# Test_Points.net
KiCad netlist of a schematic drawn in Altium Designer
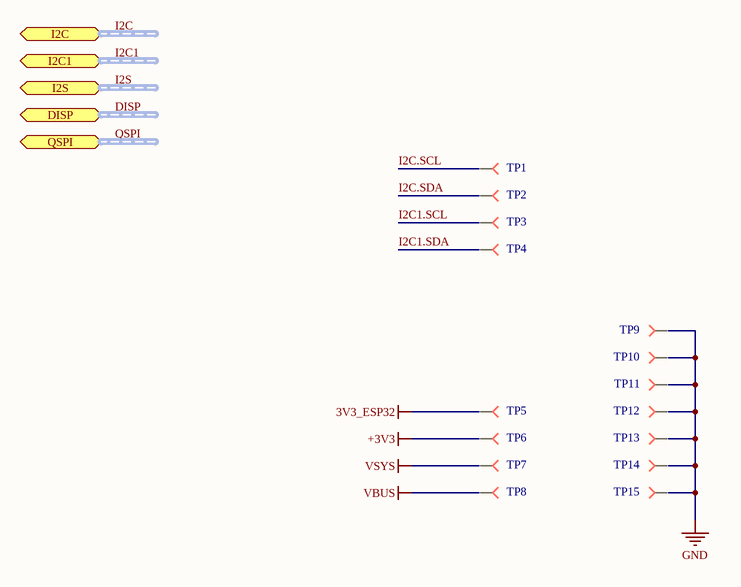
[diagram p0: Test_Points.SchDoc]

(export (version "E")
  (design (tool "Eeschema 10.0.6"))
  (components
    (comp (ref "TP1")
      (value "Test Point Pad")
      (footprint "Testpoint")
      (description "Test Point. There is nothing to buy or mount.")
      (libsource (lib "BLDC_Motor_Driver") (part "Test Point Pad"))
    )
    (comp (ref "TP2")
      (value "Test Point Pad")
      (footprint "Testpoint")
      (description "Test Point. There is nothing to buy or mount.")
      (libsource (lib "BLDC_Motor_Driver") (part "Test Point Pad"))
    )
    (comp (ref "TP3")
      (value "Test Point Pad")
      (footprint "Testpoint")
      (description "Test Point. There is nothing to buy or mount.")
      (libsource (lib "BLDC_Motor_Driver") (part "Test Point Pad"))
    )
    (comp (ref "TP4")
      (value "Test Point Pad")
      (footprint "Testpoint")
      (description "Test Point. There is nothing to buy or mount.")
      (libsource (lib "BLDC_Motor_Driver") (part "Test Point Pad"))
    )
    (comp (ref "TP5")
      (value "Test Point Pad")
      (footprint "Testpoint")
      (description "Test Point. There is nothing to buy or mount.")
      (libsource (lib "BLDC_Motor_Driver") (part "Test Point Pad"))
    )
    (comp (ref "TP6")
      (value "Test Point Pad")
      (footprint "Testpoint")
      (description "Test Point. There is nothing to buy or mount.")
      (libsource (lib "BLDC_Motor_Driver") (part "Test Point Pad"))
    )
    (comp (ref "TP7")
      (value "Test Point Pad")
      (footprint "Testpoint")
      (description "Test Point. There is nothing to buy or mount.")
      (libsource (lib "BLDC_Motor_Driver") (part "Test Point Pad"))
    )
    (comp (ref "TP8")
      (value "Test Point Pad")
      (footprint "Testpoint")
      (description "Test Point. There is nothing to buy or mount.")
      (libsource (lib "BLDC_Motor_Driver") (part "Test Point Pad"))
    )
    (comp (ref "TP9")
      (value "Test Point Pad")
      (footprint "Testpoint")
      (description "Test Point. There is nothing to buy or mount.")
      (libsource (lib "") (part "Test Point Pad_1"))
    )
    (comp (ref "TP10")
      (value "Test Point Pad")
      (footprint "Testpoint")
      (description "Test Point. There is nothing to buy or mount.")
      (libsource (lib "") (part "Test Point Pad_1"))
    )
    (comp (ref "TP11")
      (value "Test Point Pad")
      (footprint "Testpoint")
      (description "Test Point. There is nothing to buy or mount.")
      (libsource (lib "") (part "Test Point Pad_1"))
    )
    (comp (ref "TP12")
      (value "Test Point Pad")
      (footprint "Testpoint")
      (description "Test Point. There is nothing to buy or mount.")
      (libsource (lib "") (part "Test Point Pad_1"))
    )
    (comp (ref "TP13")
      (value "Test Point Pad")
      (footprint "Testpoint")
      (description "Test Point. There is nothing to buy or mount.")
      (libsource (lib "") (part "Test Point Pad_1"))
    )
    (comp (ref "TP14")
      (value "Test Point Pad")
      (footprint "Testpoint")
      (description "Test Point. There is nothing to buy or mount.")
      (libsource (lib "") (part "Test Point Pad_1"))
    )
    (comp (ref "TP15")
      (value "Test Point Pad")
      (footprint "Testpoint")
      (description "Test Point. There is nothing to buy or mount.")
      (libsource (lib "") (part "Test Point Pad_1"))
    )
  )
  (nets
    (net (code "6") (name "+3V3") (class "Default")
      (node (ref "TP6") (pin "1") (pinfunction "1_1") (pintype "passive"))
    )
    (net (code "7") (name "/I2C.SCL") (class "Default")
      (node (ref "TP1") (pin "1") (pinfunction "1_1") (pintype "passive"))
    )
    (net (code "8") (name "/I2C.SDA") (class "Default")
      (node (ref "TP2") (pin "1") (pinfunction "1_1") (pintype "passive"))
    )
    (net (code "9") (name "/I2C1.SCL") (class "Default")
      (node (ref "TP3") (pin "1") (pinfunction "1_1") (pintype "passive"))
    )
    (net (code "10") (name "/I2C1.SDA") (class "Default")
      (node (ref "TP4") (pin "1") (pinfunction "1_1") (pintype "passive"))
    )
    (net (code "16") (name "3V3_ESP32") (class "Default")
      (node (ref "TP5") (pin "1") (pinfunction "1_1") (pintype "passive"))
    )
    (net (code "17") (name "GND") (class "Default")
      (node (ref "TP10") (pin "1") (pinfunction "1_1") (pintype "passive"))
      (node (ref "TP11") (pin "1") (pinfunction "1_1") (pintype "passive"))
      (node (ref "TP12") (pin "1") (pinfunction "1_1") (pintype "passive"))
      (node (ref "TP13") (pin "1") (pinfunction "1_1") (pintype "passive"))
      (node (ref "TP14") (pin "1") (pinfunction "1_1") (pintype "passive"))
      (node (ref "TP15") (pin "1") (pinfunction "1_1") (pintype "passive"))
      (node (ref "TP9") (pin "1") (pinfunction "1_1") (pintype "passive"))
    )
    (net (code "18") (name "VBUS") (class "Default")
      (node (ref "TP8") (pin "1") (pinfunction "1_1") (pintype "passive"))
    )
    (net (code "19") (name "VSYS") (class "Default")
      (node (ref "TP7") (pin "1") (pinfunction "1_1") (pintype "passive"))
    )
  )
)
